# SJ2096POE_MIPI_CAM.net
KiCad netlist of a schematic drawn in Altium Designer
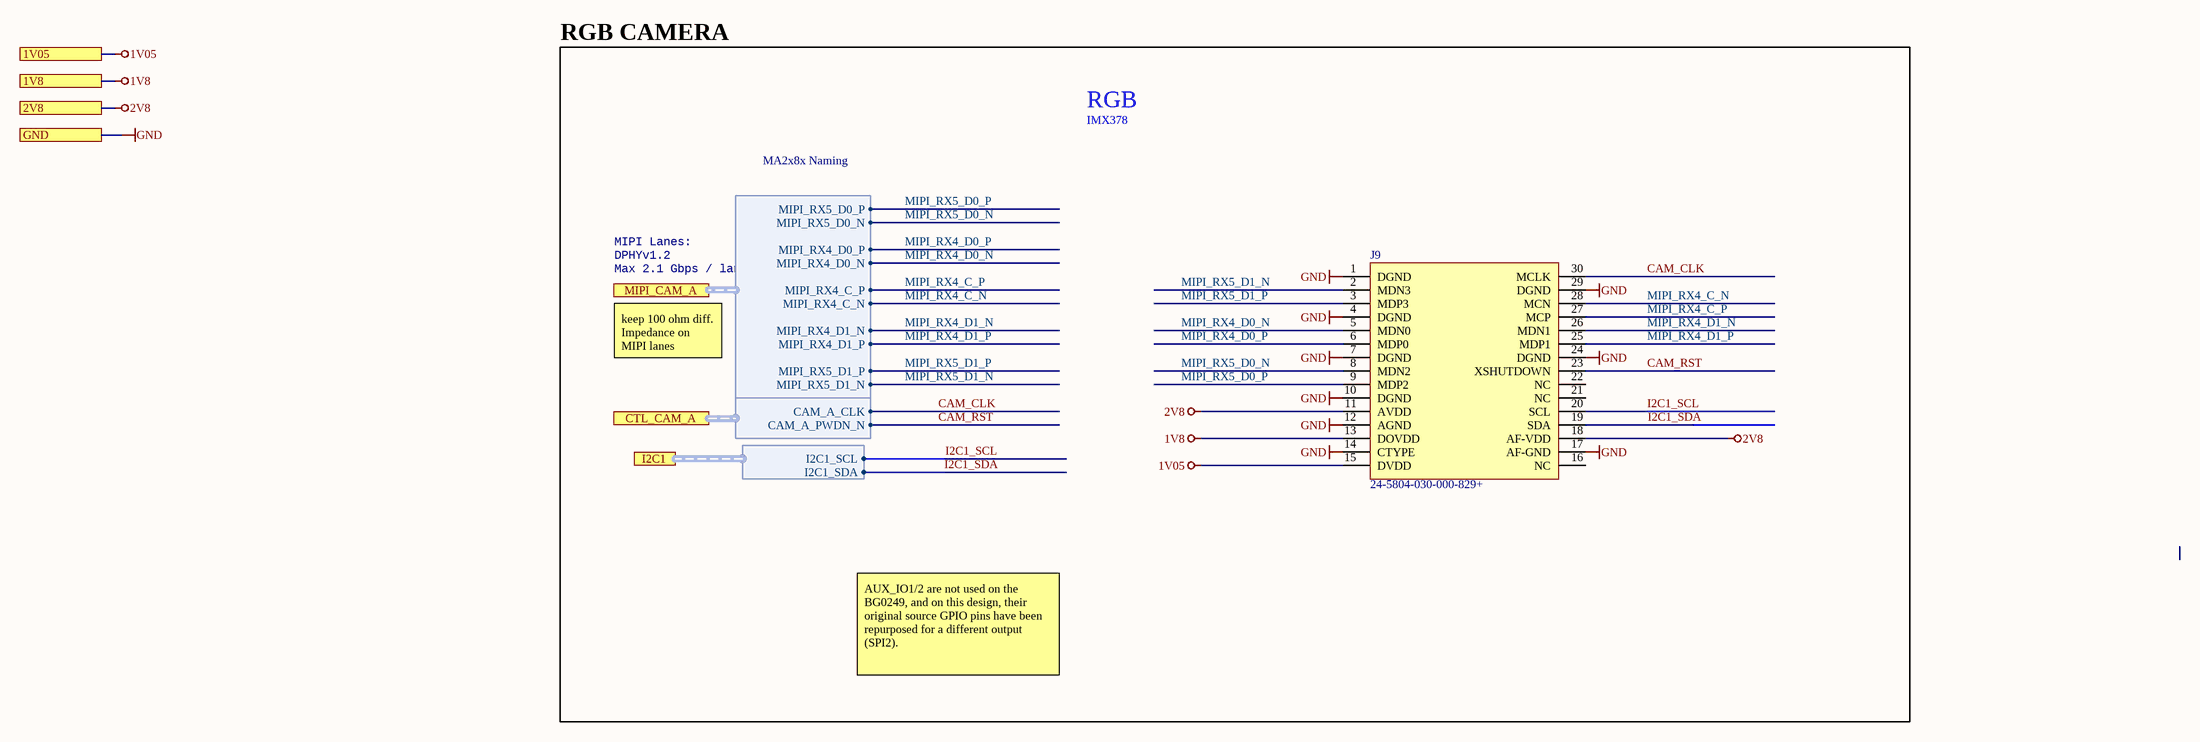
[diagram p0: SJ2096POE_MIPI_CAM.SchDoc]

(export (version "E")
  (design (tool "Eeschema 10.0.6"))
  (components
    (comp (ref "J9")
      (value "24-5804-030-000-829+")
      (footprint "BW1098OAK_R0M0E0:A12N02A-201_1.6mmbrd_MatedModule")
      (description "CONN Series 5804 board to board 0.4mm pitch 30 way connector")
      (libsource (lib "BW1098OAK_R0M0E0") (part "A12N02A-201_Connector_(1.6mm_brd)"))
    )
  )
  (nets
    (net (code "4") (name "/CAM_CLK") (class "Default")
      (node (ref "J9") (pin "30") (pinfunction "MCLK_30") (pintype "passive"))
    )
    (net (code "5") (name "/CAM_RST") (class "Default")
      (node (ref "J9") (pin "23") (pinfunction "XSHUTDOWN_23") (pintype "passive"))
    )
    (net (code "6") (name "/I2C1_SCL") (class "Default")
      (node (ref "J9") (pin "20") (pinfunction "SCL_20") (pintype "passive"))
    )
    (net (code "7") (name "/I2C1_SDA") (class "Default")
      (node (ref "J9") (pin "19") (pinfunction "SDA_19") (pintype "passive"))
    )
    (net (code "9") (name "/MIPI_RX4_C_N") (class "Default")
      (node (ref "J9") (pin "28") (pinfunction "MCN_28") (pintype "passive"))
    )
    (net (code "10") (name "/MIPI_RX4_C_P") (class "Default")
      (node (ref "J9") (pin "27") (pinfunction "MCP_27") (pintype "passive"))
    )
    (net (code "11") (name "/MIPI_RX4_D0_N") (class "Default")
      (node (ref "J9") (pin "5") (pinfunction "MDN0_5") (pintype "passive"))
    )
    (net (code "12") (name "/MIPI_RX4_D0_P") (class "Default")
      (node (ref "J9") (pin "6") (pinfunction "MDP0_6") (pintype "passive"))
    )
    (net (code "13") (name "/MIPI_RX4_D1_N") (class "Default")
      (node (ref "J9") (pin "26") (pinfunction "MDN1_26") (pintype "passive"))
    )
    (net (code "14") (name "/MIPI_RX4_D1_P") (class "Default")
      (node (ref "J9") (pin "25") (pinfunction "MDP1_25") (pintype "passive"))
    )
    (net (code "15") (name "/MIPI_RX5_D0_N") (class "Default")
      (node (ref "J9") (pin "8") (pinfunction "MDN2_8") (pintype "passive"))
    )
    (net (code "16") (name "/MIPI_RX5_D0_P") (class "Default")
      (node (ref "J9") (pin "9") (pinfunction "MDP2_9") (pintype "passive"))
    )
    (net (code "17") (name "/MIPI_RX5_D1_N") (class "Default")
      (node (ref "J9") (pin "2") (pinfunction "MDN3_2") (pintype "passive"))
    )
    (net (code "18") (name "/MIPI_RX5_D1_P") (class "Default")
      (node (ref "J9") (pin "3") (pinfunction "MDP3_3") (pintype "passive"))
    )
    (net (code "21") (name "1V05") (class "Default")
      (node (ref "J9") (pin "15") (pinfunction "DVDD_15") (pintype "passive"))
    )
    (net (code "22") (name "1V8") (class "Default")
      (node (ref "J9") (pin "13") (pinfunction "DOVDD_13") (pintype "passive"))
    )
    (net (code "23") (name "2V8") (class "Default")
      (node (ref "J9") (pin "11") (pinfunction "AVDD_11") (pintype "passive"))
      (node (ref "J9") (pin "18") (pinfunction "AF-VDD_18") (pintype "passive"))
    )
    (net (code "24") (name "GND") (class "Default")
      (node (ref "J9") (pin "1") (pinfunction "DGND_1") (pintype "passive"))
      (node (ref "J9") (pin "10") (pinfunction "DGND_10") (pintype "passive"))
      (node (ref "J9") (pin "12") (pinfunction "AGND_12") (pintype "passive"))
      (node (ref "J9") (pin "14") (pinfunction "CTYPE_14") (pintype "passive"))
      (node (ref "J9") (pin "17") (pinfunction "AF-GND_17") (pintype "passive"))
      (node (ref "J9") (pin "24") (pinfunction "DGND_24") (pintype "passive"))
      (node (ref "J9") (pin "29") (pinfunction "DGND_29") (pintype "passive"))
      (node (ref "J9") (pin "4") (pinfunction "DGND_4") (pintype "passive"))
      (node (ref "J9") (pin "7") (pinfunction "DGND_7") (pintype "passive"))
    )
    (net (code "25") (name "unconnected-(J9-NC-Pad16)") (class "Default")
      (node (ref "J9") (pin "16") (pinfunction "NC_16") (pintype "passive"))
    )
    (net (code "26") (name "unconnected-(J9-NC-Pad21)") (class "Default")
      (node (ref "J9") (pin "21") (pinfunction "NC_21") (pintype "passive"))
    )
    (net (code "27") (name "unconnected-(J9-NC-Pad22)") (class "Default")
      (node (ref "J9") (pin "22") (pinfunction "NC_22") (pintype "passive"))
    )
  )
)
